# main.net
KiCad netlist of a schematic drawn in Altium Designer
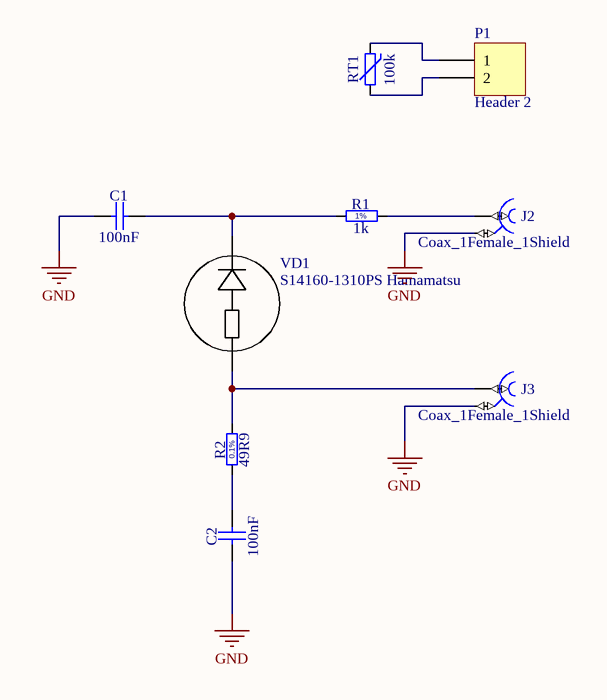
[diagram p0: main.SchDoc]

(export (version "E")
  (design (tool "Eeschema 10.0.6"))
  (components
    (comp (ref "C1")
      (value "100nF")
      (footprint "CAPC1608X90N")
      (description "Non-polarised capacitor")
      (fields
        (field (name "PART NUMBER") "CC0603_100NF_100V_10%_X7R")
        (field (name "VOLTAGE") "100V")
        (field (name "AUTHOR") "CERN DEM JLC")
      )
      (libsource (lib "Capacitors") (part "Capacitor - non polarized"))
    )
    (comp (ref "C2")
      (value "100nF")
      (footprint "CAPC1608X90N")
      (description "Non-polarised capacitor")
      (fields
        (field (name "PART NUMBER") "CC0603_100NF_100V_10%_X7R")
        (field (name "VOLTAGE") "100V")
        (field (name "AUTHOR") "CERN DEM JLC")
      )
      (libsource (lib "Capacitors") (part "Capacitor - non polarized"))
    )
    (comp (ref "J2")
      (value "Coax_1Female_1Shield")
      (footprint "HUBER-SUHNER_85_MMCX-50-0-1/111_OE")
      (fields
        (field (name "PART NUMBER") "HUBER-SUHNER_85_MMCX-50-0-1/111_OE")
        (field (name "MANUFACTURER") "HUBER+SUHNER")
        (field (name "MANUFACTURER PART NUMBER") "85_MMCX-50-0-1/111_OE")
        (field (name "AUTHOR") "CERN DEM JLC")
      )
      (libsource (lib "Connectors") (part "Coax_1Female_1Shield"))
    )
    (comp (ref "J3")
      (value "Coax_1Female_1Shield")
      (footprint "HUBER-SUHNER_85_MMCX-50-0-1/111_OE")
      (fields
        (field (name "PART NUMBER") "HUBER-SUHNER_85_MMCX-50-0-1/111_OE")
        (field (name "MANUFACTURER") "HUBER+SUHNER")
        (field (name "MANUFACTURER PART NUMBER") "85_MMCX-50-0-1/111_OE")
        (field (name "AUTHOR") "CERN DEM JLC")
      )
      (libsource (lib "Connectors") (part "Coax_1Female_1Shield"))
    )
    (comp (ref "P1")
      (value "Header 2")
      (footprint "HDR1X2")
      (description "Header, 2-Pin")
      (fields (field (name "PUBLISHER") "Altium Limited"))
      (libsource (lib "Miscellaneous Connectors") (part "Header 2"))
    )
    (comp (ref "R1")
      (value "1k")
      (footprint "RESC1608X55N")
      (description "Resistor - 1%")
      (fields
        (field (name "PART NUMBER") "R0603_1K_1%_0.1W_100PPM")
        (field (name "POWER") "0.1W")
        (field (name "AUTHOR") "CERN DEM JLC")
      )
      (libsource (lib "Resistors") (part "Resistor - 1%"))
    )
    (comp (ref "R2")
      (value "49R9")
      (footprint "RESC1608X55N")
      (description "Resistor - 0.1%")
      (fields
        (field (name "PART NUMBER") "R0603_49R9_0.1%_0.063W_10PPM")
        (field (name "POWER") "0.063W")
        (field (name "AUTHOR") "CERN DEM JLC")
      )
      (libsource (lib "Resistors") (part "Resistor - 0.1%"))
    )
    (comp (ref "RT1")
      (value "100k")
      (footprint "THERMC1608X90N")
      (description "Thermistor NTC (Negative Temperature Coefficient)")
      (fields
        (field (name "PART NUMBER") "THERM_NTC_10K_EPCOS_B57330V2103J260")
        (field (name "POWER") "180mW")
        (field (name "AUTHOR") "CERN DEM BC")
      )
      (libsource (lib "Resistors") (part "Thermistor NTC"))
    )
    (comp (ref "VD1")
      (value "S14160-1310PS Hamamatsu")
      (footprint "S14160-1310PS")
      (fields (field (name "MANUFACTURER") "Hamamatsu"))
      (libsource (lib "Schlib") (part "S14160-1310PS"))
    )
  )
  (nets
    (net (code "1") (name "GND") (class "Default")
      (node (ref "C1") (pin "1") (pinfunction "1_1") (pintype "passive"))
      (node (ref "C2") (pin "1") (pinfunction "1_1") (pintype "passive"))
      (node (ref "J2") (pin "2") (pinfunction "2_2") (pintype "bidirectional"))
      (node (ref "J3") (pin "2") (pinfunction "2_2") (pintype "bidirectional"))
    )
    (net (code "2") (name "Net-(C2-Pad2)") (class "Default")
      (node (ref "C2") (pin "2") (pinfunction "2_2") (pintype "passive"))
      (node (ref "R2") (pin "1") (pinfunction "1_1") (pintype "passive"))
    )
    (net (code "3") (name "Net-(J2-Pad1)") (class "Default")
      (node (ref "J2") (pin "1") (pinfunction "1_1") (pintype "bidirectional"))
      (node (ref "R1") (pin "2") (pinfunction "2_2") (pintype "passive"))
    )
    (net (code "4") (name "Net-(P1-Pad1)") (class "Default")
      (node (ref "P1") (pin "1") (pinfunction "1_1") (pintype "passive"))
      (node (ref "RT1") (pin "2") (pinfunction "2_2") (pintype "passive"))
    )
    (net (code "5") (name "Net-(P1-Pad2)") (class "Default")
      (node (ref "P1") (pin "2") (pinfunction "2_2") (pintype "passive"))
      (node (ref "RT1") (pin "1") (pinfunction "1_1") (pintype "passive"))
    )
    (net (code "6") (name "Net-(VD1-A)") (class "Default")
      (node (ref "J3") (pin "1") (pinfunction "1_1") (pintype "bidirectional"))
      (node (ref "R2") (pin "2") (pinfunction "2_2") (pintype "passive"))
      (node (ref "VD1") (pin "3") (pinfunction "A_3") (pintype "passive"))
    )
    (net (code "7") (name "Net-(VD1-C)") (class "Default")
      (node (ref "C1") (pin "2") (pinfunction "2_2") (pintype "passive"))
      (node (ref "R1") (pin "1") (pinfunction "1_1") (pintype "passive"))
      (node (ref "VD1") (pin "2") (pinfunction "C_2") (pintype "passive"))
    )
  )
)
